# MicroMultimeter_LED_Sch.net
KiCad netlist of a schematic drawn in Altium Designer
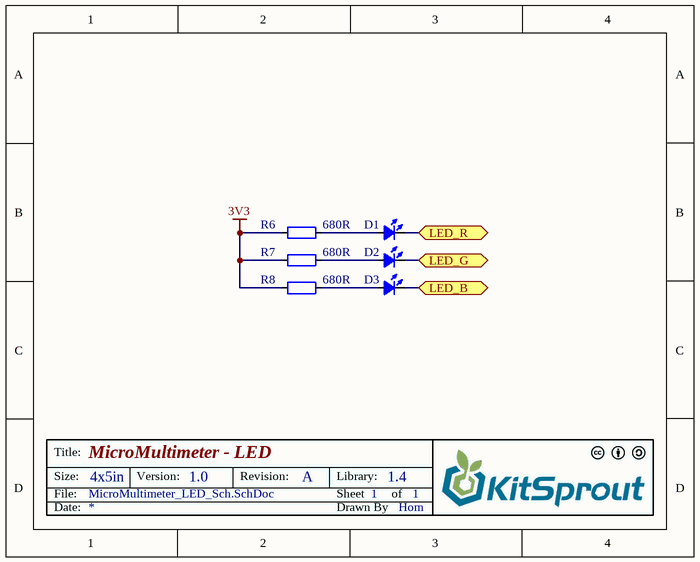
[diagram p0: MicroMultimeter_LED_Sch.SchDoc]

(export (version "E")
  (design (tool "Eeschema 10.0.6"))
  (components
    (comp (ref "D1")
      (value "LED_0603")
      (footprint "PCB_ActiveLED:LED_0603_RED")
      (description "LED")
      (libsource (lib "SCH_Active") (part "LED_0603"))
    )
    (comp (ref "D2")
      (value "LED_0603")
      (footprint "PCB_ActiveLED:LED_0603_GREEN")
      (description "LED")
      (libsource (lib "SCH_Active") (part "LED_0603"))
    )
    (comp (ref "D3")
      (value "LED_0603")
      (footprint "PCB_ActiveLED:LED_0603_BLUE")
      (description "LED")
      (libsource (lib "SCH_Active") (part "LED_0603"))
    )
    (comp (ref "R6")
      (value "680R")
      (footprint "PCB_PassiveRes:RES_0603")
      (description "Resistor")
      (fields (field (name "Comment") "Res_0603"))
      (libsource (lib "SCH_Passive") (part "Res_0603"))
    )
    (comp (ref "R7")
      (value "680R")
      (footprint "PCB_PassiveRes:RES_0603")
      (description "Resistor")
      (fields (field (name "Comment") "Res_0603"))
      (libsource (lib "SCH_Passive") (part "Res_0603"))
    )
    (comp (ref "R8")
      (value "680R")
      (footprint "PCB_PassiveRes:RES_0603")
      (description "Resistor")
      (fields (field (name "Comment") "Res_0603"))
      (libsource (lib "") (part "Res_0603_1"))
    )
  )
  (nets
    (net (code "1") (name "/LED_B") (class "Default")
      (node (ref "D3") (pin "2") (pinfunction "K_2") (pintype "passive"))
    )
    (net (code "2") (name "/LED_G") (class "Default")
      (node (ref "D2") (pin "2") (pinfunction "K_2") (pintype "passive"))
    )
    (net (code "3") (name "/LED_R") (class "Default")
      (node (ref "D1") (pin "2") (pinfunction "K_2") (pintype "passive"))
    )
    (net (code "4") (name "3V3") (class "Default")
      (node (ref "R6") (pin "2") (pinfunction "2_2") (pintype "passive"))
      (node (ref "R7") (pin "2") (pinfunction "2_2") (pintype "passive"))
      (node (ref "R8") (pin "1") (pinfunction "1_1") (pintype "passive"))
    )
    (net (code "5") (name "Net-(D1-A)") (class "Default")
      (node (ref "D1") (pin "1") (pinfunction "A_1") (pintype "passive"))
      (node (ref "R6") (pin "1") (pinfunction "1_1") (pintype "passive"))
    )
    (net (code "6") (name "Net-(D2-A)") (class "Default")
      (node (ref "D2") (pin "1") (pinfunction "A_1") (pintype "passive"))
      (node (ref "R7") (pin "1") (pinfunction "1_1") (pintype "passive"))
    )
    (net (code "7") (name "Net-(D3-A)") (class "Default")
      (node (ref "D3") (pin "1") (pinfunction "A_1") (pintype "passive"))
      (node (ref "R8") (pin "2") (pinfunction "2_2") (pintype "passive"))
    )
  )
)
